# MSP430F5528ZQFE.net
KiCad netlist of a schematic drawn in Altium Designer
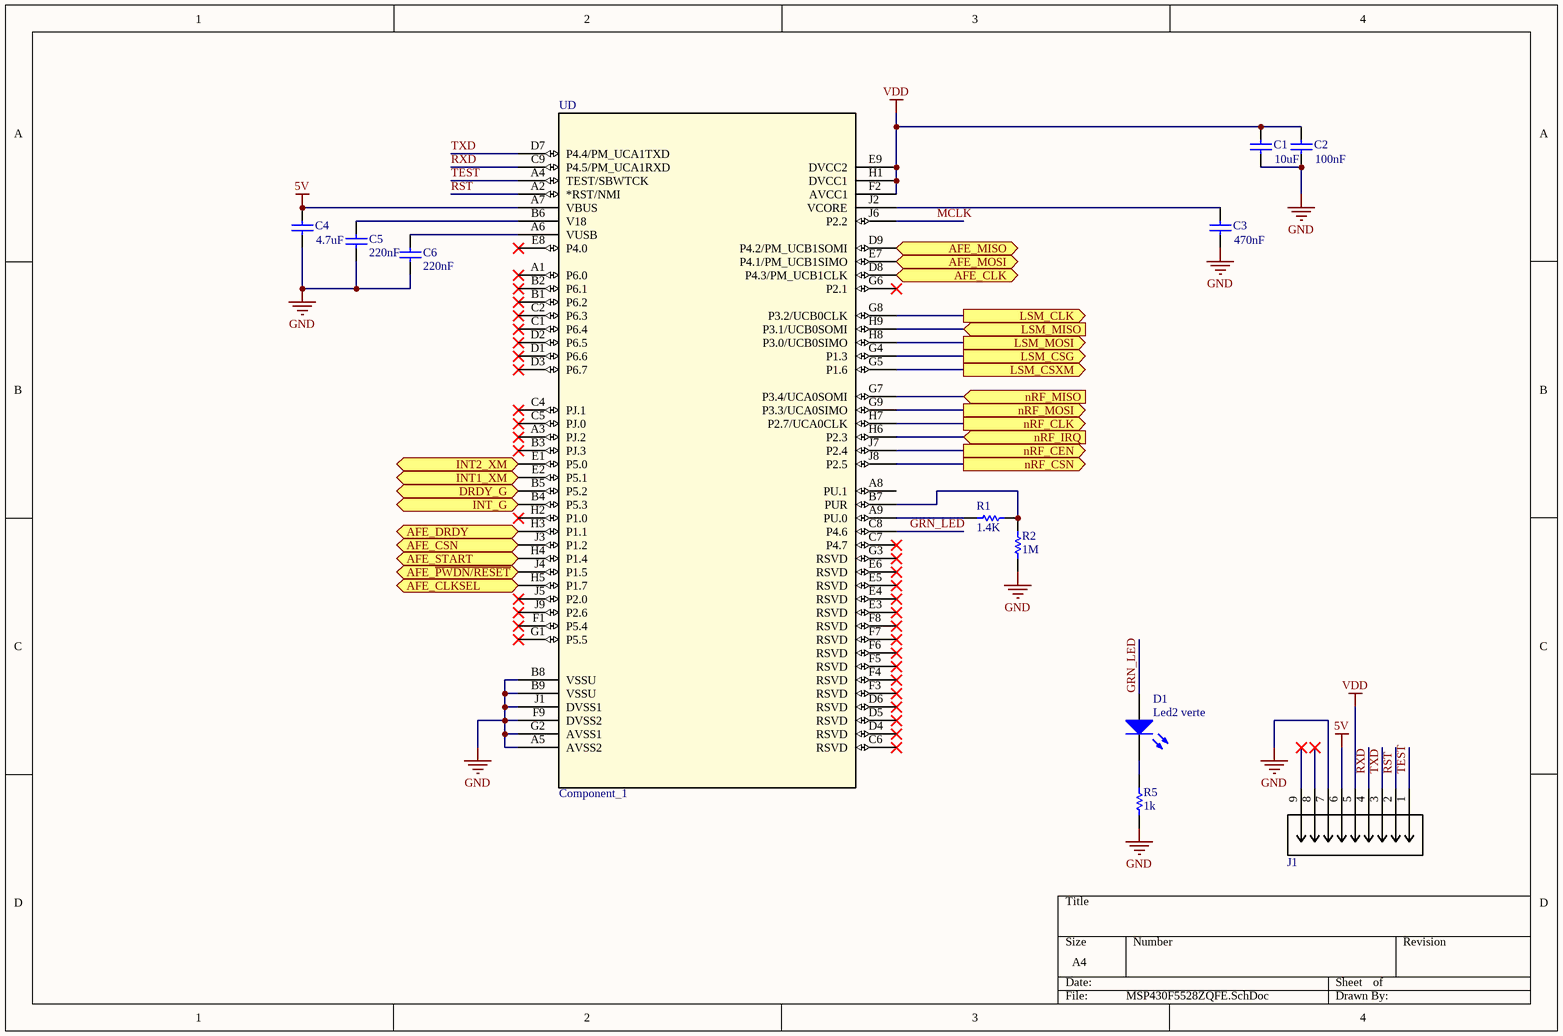
[diagram p0: MSP430F5528ZQFE.SchDoc]

(export (version "E")
  (design (tool "Eeschema 10.0.6"))
  (components
    (comp (ref "C1")
      (value "10uF")
      (footprint "0402")
      (description "Capacitor (Semiconductor SIM Model)")
      (fields (field (name "Comment") "Cap Semi") (field (name "PUBLISHER") "Altium Limited"))
      (libsource (lib "Miscellaneous Devices") (part "Cap Semi"))
    )
    (comp (ref "C2")
      (value "100nF")
      (footprint "0402")
      (description "Capacitor (Semiconductor SIM Model)")
      (fields (field (name "Comment") "Cap Semi") (field (name "PUBLISHER") "Altium Limited"))
      (libsource (lib "Miscellaneous Devices") (part "Cap Semi"))
    )
    (comp (ref "C3")
      (value "470nF")
      (footprint "0402")
      (description "Capacitor (Semiconductor SIM Model)")
      (fields (field (name "Comment") "Cap Semi") (field (name "PUBLISHER") "Altium Limited"))
      (libsource (lib "Miscellaneous Devices") (part "Cap Semi"))
    )
    (comp (ref "C4")
      (value "4.7uF")
      (footprint "0402")
      (description "Capacitor (Semiconductor SIM Model)")
      (fields (field (name "Comment") "Cap Semi") (field (name "PUBLISHER") "Altium Limited"))
      (libsource (lib "Miscellaneous Devices") (part "Cap Semi"))
    )
    (comp (ref "C5")
      (value "220nF")
      (footprint "0402")
      (description "Capacitor (Semiconductor SIM Model)")
      (fields (field (name "Comment") "Cap Semi") (field (name "PUBLISHER") "Altium Limited"))
      (libsource (lib "Miscellaneous Devices") (part "Cap Semi"))
    )
    (comp (ref "C6")
      (value "220nF")
      (footprint "0402")
      (description "Capacitor (Semiconductor SIM Model)")
      (fields (field (name "Comment") "Cap Semi") (field (name "PUBLISHER") "Altium Limited"))
      (libsource (lib "Miscellaneous Devices") (part "Cap Semi"))
    )
    (comp (ref "D1")
      (value "Led2 verte")
      (footprint "0805 (2012 metric)")
      (description "LED 2X1.2MM 570NM GN WTR CLR SMD")
      (libsource (lib "Miscellaneous Devices") (part "LED3"))
    )
    (comp (ref "J1")
      (value "FH12-7S-1SH(55)")
      (footprint "CON7_1X7_DRBF_HS")
      (description "Imported")
      (fields
        (field (name "DIGIKEYPARTNUMBER") "HFB107TR-ND")
        (field (name "COPYRIGHT") "Copyright (C) 2015 Accelerated Designs. All rights reserved")
      )
      (libsource (lib "HFB107CT-ND") (part "FH12-7S-1SH(55)"))
    )
    (comp (ref "R1")
      (value "1.4K")
      (footprint "0402")
      (description "Semiconductor Resistor")
      (fields (field (name "PUBLISHER") "Altium Limited"))
      (libsource (lib "Miscellaneous Devices") (part "Res Semi"))
    )
    (comp (ref "R2")
      (value "1M")
      (footprint "0402")
      (description "Semiconductor Resistor")
      (fields (field (name "PUBLISHER") "Altium Limited"))
      (libsource (lib "Miscellaneous Devices") (part "Res Semi"))
    )
    (comp (ref "R5")
      (value "1k")
      (footprint "0402")
      (description "Semiconductor Resistor")
      (fields (field (name "PUBLISHER") "Altium Limited"))
      (libsource (lib "Miscellaneous Devices") (part "Res Semi"))
    )
    (comp (ref "UD")
      (value "Component_1")
      (footprint "MSP430F5528ZQFE")
      (libsource (lib "MSP430F5528ZQFE") (part "Component_1"))
    )
  )
  (nets
    (net (code "1") (name "/AFE_CLK") (class "Default")
      (node (ref "UD") (pin "D8") (pinfunction "P4.3/PM_UCB1CLK_D8") (pintype "bidirectional"))
    )
    (net (code "2") (name "/AFE_CLKSEL") (class "Default")
      (node (ref "UD") (pin "H5") (pinfunction "P1.7_H5") (pintype "bidirectional"))
    )
    (net (code "3") (name "/AFE_CSN") (class "Default")
      (node (ref "UD") (pin "J3") (pinfunction "P1.2_J3") (pintype "bidirectional"))
    )
    (net (code "4") (name "/AFE_DRDY") (class "Default")
      (node (ref "UD") (pin "H3") (pinfunction "P1.1_H3") (pintype "bidirectional"))
    )
    (net (code "5") (name "/AFE_MISO") (class "Default")
      (node (ref "UD") (pin "D9") (pinfunction "P4.2/PM_UCB1SOMI_D9") (pintype "bidirectional"))
    )
    (net (code "6") (name "/AFE_MOSI") (class "Default")
      (node (ref "UD") (pin "E7") (pinfunction "P4.1/PM_UCB1SIMO_E7") (pintype "bidirectional"))
    )
    (net (code "7") (name "/AFE_START") (class "Default")
      (node (ref "UD") (pin "H4") (pinfunction "P1.4_H4") (pintype "bidirectional"))
    )
    (net (code "8") (name "/AFE_~{PWDN{slash}RESET}") (class "Default")
      (node (ref "UD") (pin "J4") (pinfunction "P1.5_J4") (pintype "bidirectional"))
    )
    (net (code "9") (name "/DRDY_G") (class "Default")
      (node (ref "UD") (pin "B5") (pinfunction "P5.2_B5") (pintype "bidirectional"))
    )
    (net (code "10") (name "/GRN_LED") (class "Default")
      (node (ref "D1") (pin "1") (pinfunction "A_1") (pintype "passive"))
      (node (ref "UD") (pin "C8") (pinfunction "P4.6_C8") (pintype "bidirectional"))
    )
    (net (code "11") (name "/INT1_XM") (class "Default")
      (node (ref "UD") (pin "E2") (pinfunction "P5.1_E2") (pintype "bidirectional"))
    )
    (net (code "12") (name "/INT2_XM") (class "Default")
      (node (ref "UD") (pin "E1") (pinfunction "P5.0_E1") (pintype "bidirectional"))
    )
    (net (code "13") (name "/INT_G") (class "Default")
      (node (ref "UD") (pin "B4") (pinfunction "P5.3_B4") (pintype "bidirectional"))
    )
    (net (code "14") (name "/LSM_CLK") (class "Default")
      (node (ref "UD") (pin "G8") (pinfunction "P3.2/UCB0CLK_G8") (pintype "bidirectional"))
    )
    (net (code "15") (name "/LSM_CSG") (class "Default")
      (node (ref "UD") (pin "G4") (pinfunction "P1.3_G4") (pintype "bidirectional"))
    )
    (net (code "16") (name "/LSM_CSXM") (class "Default")
      (node (ref "UD") (pin "G5") (pinfunction "P1.6_G5") (pintype "bidirectional"))
    )
    (net (code "17") (name "/LSM_MISO") (class "Default")
      (node (ref "UD") (pin "H9") (pinfunction "P3.1/UCB0SOMI_H9") (pintype "bidirectional"))
    )
    (net (code "18") (name "/LSM_MOSI") (class "Default")
      (node (ref "UD") (pin "H8") (pinfunction "P3.0/UCB0SIMO_H8") (pintype "bidirectional"))
    )
    (net (code "19") (name "/MCLK") (class "Default")
      (node (ref "UD") (pin "J6") (pinfunction "P2.2_J6") (pintype "bidirectional"))
    )
    (net (code "20") (name "/RST") (class "Default")
      (node (ref "J1") (pin "2") (pinfunction "2_2") (pintype "passive"))
      (node (ref "UD") (pin "A2") (pinfunction "*RST/NMI_A2") (pintype "bidirectional"))
    )
    (net (code "21") (name "/RXD") (class "Default")
      (node (ref "J1") (pin "4") (pinfunction "4_4") (pintype "passive"))
      (node (ref "UD") (pin "C9") (pinfunction "P4.5/PM_UCA1RXD_C9") (pintype "bidirectional"))
    )
    (net (code "22") (name "/TEST") (class "Default")
      (node (ref "J1") (pin "1") (pinfunction "1_1") (pintype "passive"))
      (node (ref "UD") (pin "A4") (pinfunction "TEST/SBWTCK_A4") (pintype "bidirectional"))
    )
    (net (code "23") (name "/TXD") (class "Default")
      (node (ref "J1") (pin "3") (pinfunction "3_3") (pintype "passive"))
      (node (ref "UD") (pin "D7") (pinfunction "P4.4/PM_UCA1TXD_D7") (pintype "bidirectional"))
    )
    (net (code "24") (name "/nRF_CEN") (class "Default")
      (node (ref "UD") (pin "J7") (pinfunction "P2.4_J7") (pintype "bidirectional"))
    )
    (net (code "25") (name "/nRF_CLK") (class "Default")
      (node (ref "UD") (pin "H7") (pinfunction "P2.7/UCA0CLK_H7") (pintype "bidirectional"))
    )
    (net (code "26") (name "/nRF_CSN") (class "Default")
      (node (ref "UD") (pin "J8") (pinfunction "P2.5_J8") (pintype "bidirectional"))
    )
    (net (code "27") (name "/nRF_IRQ") (class "Default")
      (node (ref "UD") (pin "H6") (pinfunction "P2.3_H6") (pintype "bidirectional"))
    )
    (net (code "28") (name "/nRF_MISO") (class "Default")
      (node (ref "UD") (pin "G7") (pinfunction "P3.4/UCA0SOMI_G7") (pintype "bidirectional"))
    )
    (net (code "29") (name "/nRF_MOSI") (class "Default")
      (node (ref "UD") (pin "G9") (pinfunction "P3.3/UCA0SIMO_G9") (pintype "bidirectional"))
    )
    (net (code "30") (name "5V") (class "Default")
      (node (ref "C4") (pin "1") (pinfunction "1_1") (pintype "passive"))
      (node (ref "J1") (pin "6") (pinfunction "6_6") (pintype "passive"))
      (node (ref "UD") (pin "A7") (pinfunction "VBUS_A7") (pintype "power_in"))
    )
    (net (code "31") (name "GND") (class "Default")
      (node (ref "C1") (pin "2") (pinfunction "2_2") (pintype "passive"))
      (node (ref "C2") (pin "2") (pinfunction "2_2") (pintype "passive"))
      (node (ref "C3") (pin "2") (pinfunction "2_2") (pintype "passive"))
      (node (ref "C4") (pin "2") (pinfunction "2_2") (pintype "passive"))
      (node (ref "C5") (pin "1") (pinfunction "1_1") (pintype "passive"))
      (node (ref "C6") (pin "1") (pinfunction "1_1") (pintype "passive"))
      (node (ref "J1") (pin "7") (pinfunction "7_7") (pintype "passive"))
      (node (ref "R2") (pin "2") (pinfunction "2_2") (pintype "passive"))
      (node (ref "R5") (pin "2") (pinfunction "2_2") (pintype "passive"))
      (node (ref "UD") (pin "A5") (pinfunction "AVSS2_A5") (pintype "power_in"))
      (node (ref "UD") (pin "B8") (pinfunction "VSSU_B8") (pintype "power_in"))
      (node (ref "UD") (pin "B9") (pinfunction "VSSU_B9") (pintype "power_in"))
      (node (ref "UD") (pin "F9") (pinfunction "DVSS2_F9") (pintype "power_in"))
      (node (ref "UD") (pin "G2") (pinfunction "AVSS1_G2") (pintype "power_in"))
      (node (ref "UD") (pin "J1") (pinfunction "DVSS1_J1") (pintype "power_in"))
    )
    (net (code "32") (name "Net-(D1-K)") (class "Default")
      (node (ref "D1") (pin "2") (pinfunction "K_2") (pintype "passive"))
      (node (ref "R5") (pin "1") (pinfunction "1_1") (pintype "passive"))
    )
    (net (code "33") (name "Net-(UD-PU.0)") (class "Default")
      (node (ref "R1") (pin "2") (pinfunction "2_2") (pintype "passive"))
      (node (ref "UD") (pin "A9") (pinfunction "PU.0_A9") (pintype "bidirectional"))
    )
    (net (code "34") (name "Net-(UD-PUR)") (class "Default")
      (node (ref "R1") (pin "1") (pinfunction "1_1") (pintype "passive"))
      (node (ref "R2") (pin "1") (pinfunction "1_1") (pintype "passive"))
      (node (ref "UD") (pin "B7") (pinfunction "PUR_B7") (pintype "bidirectional"))
    )
    (net (code "35") (name "Net-(UD-V18)") (class "Default")
      (node (ref "C5") (pin "2") (pinfunction "2_2") (pintype "passive"))
      (node (ref "UD") (pin "B6") (pinfunction "V18_B6") (pintype "power_in"))
    )
    (net (code "36") (name "Net-(UD-VCORE)") (class "Default")
      (node (ref "C3") (pin "1") (pinfunction "1_1") (pintype "passive"))
      (node (ref "UD") (pin "J2") (pinfunction "VCORE_J2") (pintype "power_in"))
    )
    (net (code "37") (name "Net-(UD-VUSB)") (class "Default")
      (node (ref "C6") (pin "2") (pinfunction "2_2") (pintype "passive"))
      (node (ref "UD") (pin "A6") (pinfunction "VUSB_A6") (pintype "power_in"))
    )
    (net (code "38") (name "VDD") (class "Default")
      (node (ref "C1") (pin "1") (pinfunction "1_1") (pintype "passive"))
      (node (ref "C2") (pin "1") (pinfunction "1_1") (pintype "passive"))
      (node (ref "J1") (pin "5") (pinfunction "5_5") (pintype "passive"))
      (node (ref "UD") (pin "E9") (pinfunction "DVCC2_E9") (pintype "power_in"))
      (node (ref "UD") (pin "F2") (pinfunction "AVCC1_F2") (pintype "power_in"))
      (node (ref "UD") (pin "H1") (pinfunction "DVCC1_H1") (pintype "power_in"))
    )
    (net (code "39") (name "unconnected-(J1-Pad8)") (class "Default")
      (node (ref "J1") (pin "8") (pinfunction "8_8") (pintype "passive+no_connect"))
    )
    (net (code "40") (name "unconnected-(J1-Pad9)") (class "Default")
      (node (ref "J1") (pin "9") (pinfunction "9_9") (pintype "passive+no_connect"))
    )
    (net (code "41") (name "unconnected-(UD-P1.0-PadH2)") (class "Default")
      (node (ref "UD") (pin "H2") (pinfunction "P1.0_H2") (pintype "bidirectional+no_connect"))
    )
    (net (code "42") (name "unconnected-(UD-P2.0-PadJ5)") (class "Default")
      (node (ref "UD") (pin "J5") (pinfunction "P2.0_J5") (pintype "bidirectional+no_connect"))
    )
    (net (code "43") (name "unconnected-(UD-P2.1-PadG6)") (class "Default")
      (node (ref "UD") (pin "G6") (pinfunction "P2.1_G6") (pintype "bidirectional+no_connect"))
    )
    (net (code "44") (name "unconnected-(UD-P2.6-PadJ9)") (class "Default")
      (node (ref "UD") (pin "J9") (pinfunction "P2.6_J9") (pintype "bidirectional+no_connect"))
    )
    (net (code "45") (name "unconnected-(UD-P4.0-PadE8)") (class "Default")
      (node (ref "UD") (pin "E8") (pinfunction "P4.0_E8") (pintype "bidirectional+no_connect"))
    )
    (net (code "46") (name "unconnected-(UD-P4.7-PadC7)") (class "Default")
      (node (ref "UD") (pin "C7") (pinfunction "P4.7_C7") (pintype "bidirectional+no_connect"))
    )
    (net (code "47") (name "unconnected-(UD-P5.4-PadF1)") (class "Default")
      (node (ref "UD") (pin "F1") (pinfunction "P5.4_F1") (pintype "bidirectional+no_connect"))
    )
    (net (code "48") (name "unconnected-(UD-P5.5-PadG1)") (class "Default")
      (node (ref "UD") (pin "G1") (pinfunction "P5.5_G1") (pintype "bidirectional+no_connect"))
    )
    (net (code "49") (name "unconnected-(UD-P6.0-PadA1)") (class "Default")
      (node (ref "UD") (pin "A1") (pinfunction "P6.0_A1") (pintype "bidirectional+no_connect"))
    )
    (net (code "50") (name "unconnected-(UD-P6.1-PadB2)") (class "Default")
      (node (ref "UD") (pin "B2") (pinfunction "P6.1_B2") (pintype "bidirectional+no_connect"))
    )
    (net (code "51") (name "unconnected-(UD-P6.2-PadB1)") (class "Default")
      (node (ref "UD") (pin "B1") (pinfunction "P6.2_B1") (pintype "bidirectional+no_connect"))
    )
    (net (code "52") (name "unconnected-(UD-P6.3-PadC2)") (class "Default")
      (node (ref "UD") (pin "C2") (pinfunction "P6.3_C2") (pintype "bidirectional+no_connect"))
    )
    (net (code "53") (name "unconnected-(UD-P6.4-PadC1)") (class "Default")
      (node (ref "UD") (pin "C1") (pinfunction "P6.4_C1") (pintype "bidirectional+no_connect"))
    )
    (net (code "54") (name "unconnected-(UD-P6.5-PadD2)") (class "Default")
      (node (ref "UD") (pin "D2") (pinfunction "P6.5_D2") (pintype "bidirectional+no_connect"))
    )
    (net (code "55") (name "unconnected-(UD-P6.6-PadD1)") (class "Default")
      (node (ref "UD") (pin "D1") (pinfunction "P6.6_D1") (pintype "bidirectional+no_connect"))
    )
    (net (code "56") (name "unconnected-(UD-P6.7-PadD3)") (class "Default")
      (node (ref "UD") (pin "D3") (pinfunction "P6.7_D3") (pintype "bidirectional+no_connect"))
    )
    (net (code "57") (name "unconnected-(UD-PJ.0-PadC5)") (class "Default")
      (node (ref "UD") (pin "C5") (pinfunction "PJ.0_C5") (pintype "bidirectional+no_connect"))
    )
    (net (code "58") (name "unconnected-(UD-PJ.1-PadC4)") (class "Default")
      (node (ref "UD") (pin "C4") (pinfunction "PJ.1_C4") (pintype "bidirectional+no_connect"))
    )
    (net (code "59") (name "unconnected-(UD-PJ.2-PadA3)") (class "Default")
      (node (ref "UD") (pin "A3") (pinfunction "PJ.2_A3") (pintype "bidirectional+no_connect"))
    )
    (net (code "60") (name "unconnected-(UD-PJ.3-PadB3)") (class "Default")
      (node (ref "UD") (pin "B3") (pinfunction "PJ.3_B3") (pintype "bidirectional+no_connect"))
    )
    (net (code "61") (name "unconnected-(UD-PU.1-PadA8)") (class "Default")
      (node (ref "UD") (pin "A8") (pinfunction "PU.1_A8") (pintype "bidirectional"))
    )
    (net (code "62") (name "unconnected-(UD-RSVD-PadC6)") (class "Default")
      (node (ref "UD") (pin "C6") (pinfunction "RSVD_C6") (pintype "bidirectional+no_connect"))
    )
    (net (code "63") (name "unconnected-(UD-RSVD-PadD4)") (class "Default")
      (node (ref "UD") (pin "D4") (pinfunction "RSVD_D4") (pintype "bidirectional+no_connect"))
    )
    (net (code "64") (name "unconnected-(UD-RSVD-PadD5)") (class "Default")
      (node (ref "UD") (pin "D5") (pinfunction "RSVD_D5") (pintype "bidirectional+no_connect"))
    )
    (net (code "65") (name "unconnected-(UD-RSVD-PadD6)") (class "Default")
      (node (ref "UD") (pin "D6") (pinfunction "RSVD_D6") (pintype "bidirectional+no_connect"))
    )
    (net (code "66") (name "unconnected-(UD-RSVD-PadE3)") (class "Default")
      (node (ref "UD") (pin "E3") (pinfunction "RSVD_E3") (pintype "bidirectional+no_connect"))
    )
    (net (code "67") (name "unconnected-(UD-RSVD-PadE4)") (class "Default")
      (node (ref "UD") (pin "E4") (pinfunction "RSVD_E4") (pintype "bidirectional+no_connect"))
    )
    (net (code "68") (name "unconnected-(UD-RSVD-PadE5)") (class "Default")
      (node (ref "UD") (pin "E5") (pinfunction "RSVD_E5") (pintype "bidirectional+no_connect"))
    )
    (net (code "69") (name "unconnected-(UD-RSVD-PadE6)") (class "Default")
      (node (ref "UD") (pin "E6") (pinfunction "RSVD_E6") (pintype "bidirectional+no_connect"))
    )
    (net (code "70") (name "unconnected-(UD-RSVD-PadF3)") (class "Default")
      (node (ref "UD") (pin "F3") (pinfunction "RSVD_F3") (pintype "bidirectional+no_connect"))
    )
    (net (code "71") (name "unconnected-(UD-RSVD-PadF4)") (class "Default")
      (node (ref "UD") (pin "F4") (pinfunction "RSVD_F4") (pintype "bidirectional+no_connect"))
    )
    (net (code "72") (name "unconnected-(UD-RSVD-PadF5)") (class "Default")
      (node (ref "UD") (pin "F5") (pinfunction "RSVD_F5") (pintype "bidirectional+no_connect"))
    )
    (net (code "73") (name "unconnected-(UD-RSVD-PadF6)") (class "Default")
      (node (ref "UD") (pin "F6") (pinfunction "RSVD_F6") (pintype "bidirectional+no_connect"))
    )
    (net (code "74") (name "unconnected-(UD-RSVD-PadF7)") (class "Default")
      (node (ref "UD") (pin "F7") (pinfunction "RSVD_F7") (pintype "bidirectional+no_connect"))
    )
    (net (code "75") (name "unconnected-(UD-RSVD-PadF8)") (class "Default")
      (node (ref "UD") (pin "F8") (pinfunction "RSVD_F8") (pintype "bidirectional+no_connect"))
    )
    (net (code "76") (name "unconnected-(UD-RSVD-PadG3)") (class "Default")
      (node (ref "UD") (pin "G3") (pinfunction "RSVD_G3") (pintype "bidirectional+no_connect"))
    )
  )
)
